# drive_ctrl.net
KiCad netlist of a schematic drawn in EAGLE
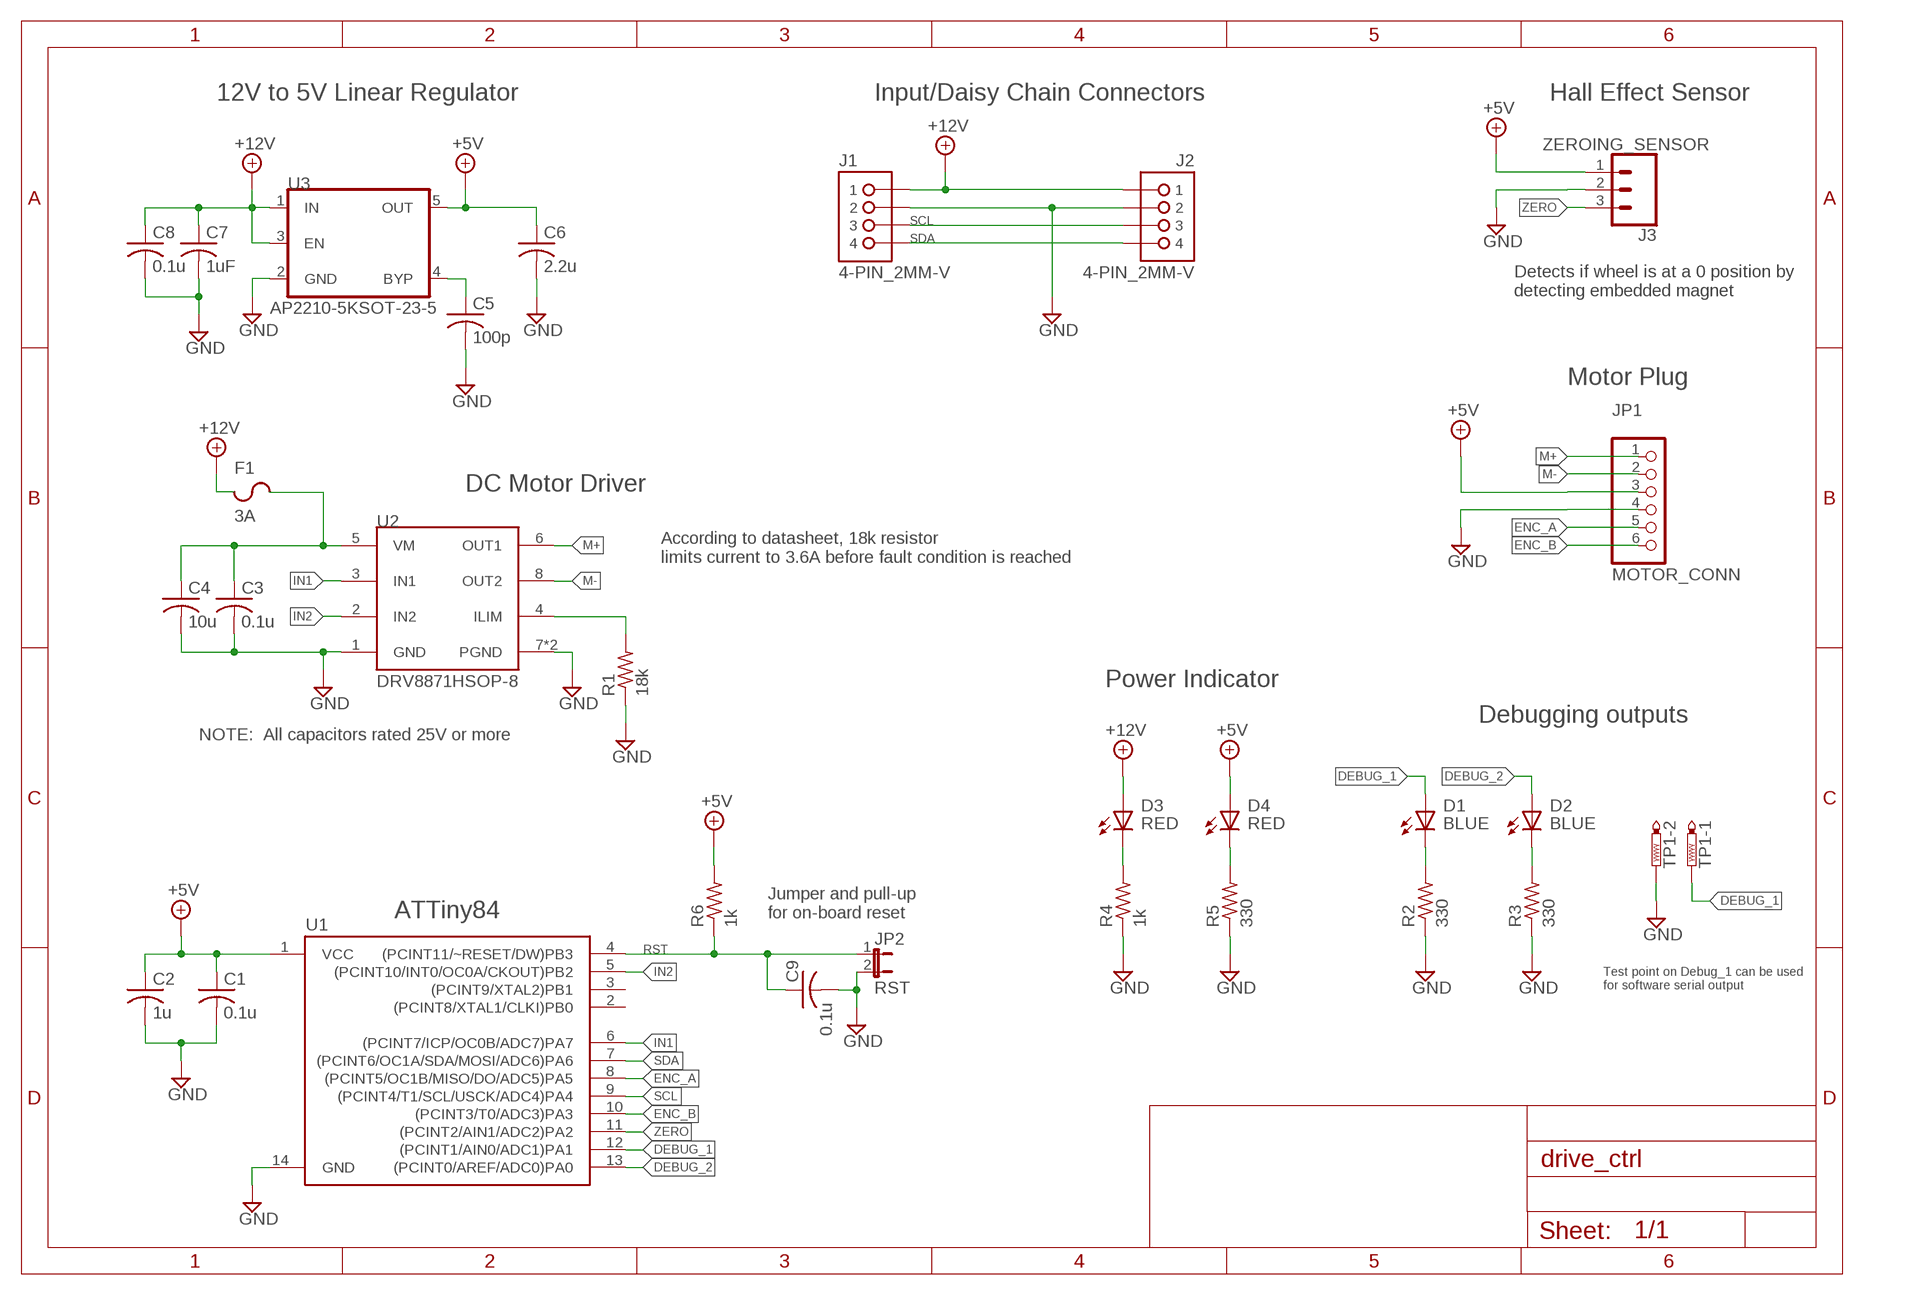
[diagram p0: schematic, sheet 1]

(export (version "E")
  (design (tool "Eeschema 10.0.6"))
  (components
    (comp (ref "C1")
      (value "0.1u")
      (footprint "eagle-import:C0603")
      (libsource (lib "eagle-import") (part "C-USC0603"))
    )
    (comp (ref "C2")
      (value "1u")
      (footprint "eagle-import:C0603")
      (libsource (lib "eagle-import") (part "C-USC0603"))
    )
    (comp (ref "C3")
      (value "0.1u")
      (footprint "eagle-import:C0603")
      (libsource (lib "eagle-import") (part "C-USC0603"))
    )
    (comp (ref "C4")
      (value "10u")
      (footprint "eagle-import:C0603")
      (libsource (lib "eagle-import") (part "C-USC0603"))
    )
    (comp (ref "C5")
      (value "100p")
      (footprint "eagle-import:C0603")
      (libsource (lib "eagle-import") (part "C-USC0603"))
    )
    (comp (ref "C6")
      (value "2.2u")
      (footprint "eagle-import:C0603")
      (libsource (lib "eagle-import") (part "C-USC0603"))
    )
    (comp (ref "C7")
      (value "1uF")
      (footprint "eagle-import:C0603")
      (libsource (lib "eagle-import") (part "C-USC0603"))
    )
    (comp (ref "C8")
      (value "0.1u")
      (footprint "eagle-import:C0603")
      (libsource (lib "eagle-import") (part "C-USC0603"))
    )
    (comp (ref "C9")
      (value "0.1u")
      (footprint "eagle-import:C0603")
      (libsource (lib "eagle-import") (part "C-USC0603"))
    )
    (comp (ref "D1")
      (value "BLUE")
      (footprint "eagle-import:CHIP-LED0603")
      (fields (field (name "MPN") "LTST-C191TBKT"))
      (libsource (lib "eagle-import") (part "LED-SMD-BLUE"))
    )
    (comp (ref "D2")
      (value "BLUE")
      (footprint "eagle-import:CHIP-LED0603")
      (fields (field (name "MPN") "LTST-C191TBKT"))
      (libsource (lib "eagle-import") (part "LED-SMD-BLUE"))
    )
    (comp (ref "D3")
      (value "RED")
      (footprint "eagle-import:CHIP-LED0603")
      (fields (field (name "MPN") "LTST-C191KRKT"))
      (libsource (lib "eagle-import") (part "LED-SMD-RED"))
    )
    (comp (ref "D4")
      (value "RED")
      (footprint "eagle-import:CHIP-LED0603")
      (fields (field (name "MPN") "LTST-C191KRKT"))
      (libsource (lib "eagle-import") (part "LED-SMD-RED"))
    )
    (comp (ref "F1")
      (value "3A")
      (footprint "eagle-import:F1206")
      (libsource (lib "eagle-import") (part "CHIP_FUSE1206"))
    )
    (comp (ref "J1")
      (value "4-PIN_2MM-V")
      (footprint "eagle-import:2MM-4-V")
      (libsource (lib "eagle-import") (part "4-PIN_2MM-V"))
    )
    (comp (ref "J2")
      (value "4-PIN_2MM-V")
      (footprint "eagle-import:2MM-4-V")
      (libsource (lib "eagle-import") (part "4-PIN_2MM-V"))
    )
    (comp (ref "J3")
      (value "ZEROING_SENSOR")
      (footprint "eagle-import:1X03")
      (libsource (lib "eagle-import") (part "CONN_03"))
    )
    (comp (ref "JP1")
      (value "MOTOR_CONN")
      (footprint "eagle-import:1X06")
      (libsource (lib "eagle-import") (part "PINHD-1X6"))
    )
    (comp (ref "JP2")
      (value "RST")
      (footprint "eagle-import:JP1")
      (libsource (lib "eagle-import") (part "JP1E"))
    )
    (comp (ref "R1")
      (value "18k")
      (footprint "eagle-import:R0603")
      (libsource (lib "eagle-import") (part "R-US_R0603"))
    )
    (comp (ref "R2")
      (value "330")
      (footprint "eagle-import:R0603")
      (libsource (lib "eagle-import") (part "R-US_R0603"))
    )
    (comp (ref "R3")
      (value "330")
      (footprint "eagle-import:R0603")
      (libsource (lib "eagle-import") (part "R-US_R0603"))
    )
    (comp (ref "R4")
      (value "1k")
      (footprint "eagle-import:R0603")
      (libsource (lib "eagle-import") (part "R-US_R0603"))
    )
    (comp (ref "R5")
      (value "330")
      (footprint "eagle-import:R0603")
      (libsource (lib "eagle-import") (part "R-US_R0603"))
    )
    (comp (ref "R6")
      (value "1k")
      (footprint "eagle-import:R0603")
      (libsource (lib "eagle-import") (part "R-US_R0603"))
    )
    (comp (ref "TP1")
      (value "PTR2")
      (footprint "eagle-import:P2-38-17")
      (libsource (lib "eagle-import") (part "PTR2"))
    )
    (comp (ref "U1")
      (value "ATTINY84ATTINY84-20PU")
      (footprint "eagle-import:DIP14")
      (libsource (lib "eagle-import") (part "ATTINY84ATTINY84-20PU"))
    )
    (comp (ref "U2")
      (value "DRV8871HSOP-8")
      (footprint "eagle-import:SOIC127P600X170-9T240X310N")
      (libsource (lib "eagle-import") (part "DRV8871HSOP-8"))
    )
    (comp (ref "U3")
      (value "AP2210-5KSOT-23-5")
      (footprint "eagle-import:SOT95P282X145-5N")
      (libsource (lib "eagle-import") (part "AP2210-5KSOT-23-5"))
    )
  )
  (nets
    (net (code "1") (name "+5V") (class "Default")
      (node (ref "C1") (pin "1") (pinfunction "1_1") (pintype "passive"))
      (node (ref "C2") (pin "1") (pinfunction "1_1") (pintype "passive"))
      (node (ref "C6") (pin "1") (pinfunction "1_1") (pintype "passive"))
      (node (ref "D4") (pin "A") (pinfunction "A_A") (pintype "passive"))
      (node (ref "J3") (pin "1") (pinfunction "1_1") (pintype "passive"))
      (node (ref "JP1") (pin "3") (pinfunction "3_3") (pintype "passive"))
      (node (ref "R6") (pin "2") (pinfunction "2_2") (pintype "passive"))
      (node (ref "U1") (pin "1") (pinfunction "VCC_1") (pintype "bidirectional"))
      (node (ref "U3") (pin "5") (pinfunction "OUT_5") (pintype "power_in"))
    )
    (net (code "2") (name "+12V") (class "Default")
      (node (ref "C7") (pin "1") (pinfunction "1_1") (pintype "passive"))
      (node (ref "C8") (pin "1") (pinfunction "1_1") (pintype "passive"))
      (node (ref "D3") (pin "A") (pinfunction "A_A") (pintype "passive"))
      (node (ref "F1") (pin "1") (pinfunction "1_1") (pintype "bidirectional"))
      (node (ref "J1") (pin "1") (pinfunction "1_1") (pintype "passive"))
      (node (ref "J2") (pin "1") (pinfunction "1_1") (pintype "passive"))
      (node (ref "U3") (pin "1") (pinfunction "IN_1") (pintype "power_in"))
      (node (ref "U3") (pin "3") (pinfunction "EN_3") (pintype "input"))
    )
    (net (code "3") (name "/RST") (class "Default")
      (node (ref "C9") (pin "1") (pinfunction "1_1") (pintype "passive"))
      (node (ref "JP2") (pin "1") (pinfunction "1_1") (pintype "passive"))
      (node (ref "R6") (pin "1") (pinfunction "1_1") (pintype "passive"))
      (node (ref "U1") (pin "4") (pinfunction "(PCINT11/~{RESET/DW})PB3_4") (pintype "bidirectional"))
    )
    (net (code "4") (name "DEBUG_1") (class "Default")
      (node (ref "D1") (pin "A") (pinfunction "A_A") (pintype "passive"))
      (node (ref "TP1") (pin "TP-1") (pinfunction "TP_TP-1") (pintype "input"))
      (node (ref "U1") (pin "12") (pinfunction "(PCINT1/AIN0/ADC1)PA1_12") (pintype "bidirectional"))
    )
    (net (code "5") (name "DEBUG_2") (class "Default")
      (node (ref "D2") (pin "A") (pinfunction "A_A") (pintype "passive"))
      (node (ref "U1") (pin "13") (pinfunction "(PCINT0/AREF/ADC0)PA0_13") (pintype "bidirectional"))
    )
    (net (code "6") (name "ENC_A") (class "Default")
      (node (ref "JP1") (pin "5") (pinfunction "5_5") (pintype "passive"))
      (node (ref "U1") (pin "8") (pinfunction "(PCINT5/OC1B/MISO/DO/ADC5)PA5_8") (pintype "bidirectional"))
    )
    (net (code "7") (name "ENC_B") (class "Default")
      (node (ref "JP1") (pin "6") (pinfunction "6_6") (pintype "passive"))
      (node (ref "U1") (pin "10") (pinfunction "(PCINT3/T0/ADC3)PA3_10") (pintype "bidirectional"))
    )
    (net (code "8") (name "GND") (class "Default")
      (node (ref "C1") (pin "2") (pinfunction "2_2") (pintype "passive"))
      (node (ref "C2") (pin "2") (pinfunction "2_2") (pintype "passive"))
      (node (ref "C3") (pin "2") (pinfunction "2_2") (pintype "passive"))
      (node (ref "C4") (pin "2") (pinfunction "2_2") (pintype "passive"))
      (node (ref "C5") (pin "2") (pinfunction "2_2") (pintype "passive"))
      (node (ref "C6") (pin "2") (pinfunction "2_2") (pintype "passive"))
      (node (ref "C7") (pin "2") (pinfunction "2_2") (pintype "passive"))
      (node (ref "C8") (pin "2") (pinfunction "2_2") (pintype "passive"))
      (node (ref "C9") (pin "2") (pinfunction "2_2") (pintype "passive"))
      (node (ref "J1") (pin "2") (pinfunction "2_2") (pintype "passive"))
      (node (ref "J2") (pin "2") (pinfunction "2_2") (pintype "passive"))
      (node (ref "J3") (pin "2") (pinfunction "2_2") (pintype "passive"))
      (node (ref "JP1") (pin "4") (pinfunction "4_4") (pintype "passive"))
      (node (ref "JP2") (pin "2") (pinfunction "2_2") (pintype "passive"))
      (node (ref "R1") (pin "1") (pinfunction "1_1") (pintype "passive"))
      (node (ref "R2") (pin "1") (pinfunction "1_1") (pintype "passive"))
      (node (ref "R3") (pin "1") (pinfunction "1_1") (pintype "passive"))
      (node (ref "R4") (pin "1") (pinfunction "1_1") (pintype "passive"))
      (node (ref "R5") (pin "1") (pinfunction "1_1") (pintype "passive"))
      (node (ref "TP1") (pin "TP-2") (pinfunction "TP_TP-2") (pintype "input"))
      (node (ref "U1") (pin "14") (pinfunction "GND_14") (pintype "bidirectional"))
      (node (ref "U2") (pin "1") (pinfunction "GND_1") (pintype "power_in"))
      (node (ref "U2") (pin "7") (pinfunction "PGND_7") (pintype "power_in"))
      (node (ref "U2") (pin "9") (pinfunction "PGND_9") (pintype "power_in"))
      (node (ref "U3") (pin "2") (pinfunction "GND_2") (pintype "power_in"))
    )
    (net (code "9") (name "IN1") (class "Default")
      (node (ref "U1") (pin "6") (pinfunction "(PCINT7/ICP/OC0B/ADC7)PA7_6") (pintype "bidirectional"))
      (node (ref "U2") (pin "3") (pinfunction "IN1_3") (pintype "input"))
    )
    (net (code "10") (name "IN2") (class "Default")
      (node (ref "U1") (pin "5") (pinfunction "(PCINT10/INT0/OC0A/CKOUT)PB2_5") (pintype "bidirectional"))
      (node (ref "U2") (pin "2") (pinfunction "IN2_2") (pintype "input"))
    )
    (net (code "11") (name "M+") (class "Default")
      (node (ref "JP1") (pin "1") (pinfunction "1_1") (pintype "passive"))
      (node (ref "U2") (pin "6") (pinfunction "OUT1_6") (pintype "output"))
    )
    (net (code "12") (name "M-") (class "Default")
      (node (ref "JP1") (pin "2") (pinfunction "2_2") (pintype "passive"))
      (node (ref "U2") (pin "8") (pinfunction "OUT2_8") (pintype "output"))
    )
    (net (code "13") (name "Net-(D1-K)") (class "Default")
      (node (ref "D1") (pin "C") (pinfunction "K_C") (pintype "passive"))
      (node (ref "R2") (pin "2") (pinfunction "2_2") (pintype "passive"))
    )
    (net (code "14") (name "Net-(D2-K)") (class "Default")
      (node (ref "D2") (pin "C") (pinfunction "K_C") (pintype "passive"))
      (node (ref "R3") (pin "2") (pinfunction "2_2") (pintype "passive"))
    )
    (net (code "15") (name "Net-(D3-K)") (class "Default")
      (node (ref "D3") (pin "C") (pinfunction "K_C") (pintype "passive"))
      (node (ref "R4") (pin "2") (pinfunction "2_2") (pintype "passive"))
    )
    (net (code "16") (name "Net-(D4-K)") (class "Default")
      (node (ref "D4") (pin "C") (pinfunction "K_C") (pintype "passive"))
      (node (ref "R5") (pin "2") (pinfunction "2_2") (pintype "passive"))
    )
    (net (code "17") (name "Net-(U2-ILIM)") (class "Default")
      (node (ref "R1") (pin "2") (pinfunction "2_2") (pintype "passive"))
      (node (ref "U2") (pin "4") (pinfunction "ILIM_4") (pintype "passive"))
    )
    (net (code "18") (name "Net-(U2-VM)") (class "Default")
      (node (ref "C3") (pin "1") (pinfunction "1_1") (pintype "passive"))
      (node (ref "C4") (pin "1") (pinfunction "1_1") (pintype "passive"))
      (node (ref "F1") (pin "2") (pinfunction "2_2") (pintype "bidirectional"))
      (node (ref "U2") (pin "5") (pinfunction "VM_5") (pintype "power_in"))
    )
    (net (code "19") (name "Net-(U3-BYP)") (class "Default")
      (node (ref "C5") (pin "1") (pinfunction "1_1") (pintype "passive"))
      (node (ref "U3") (pin "4") (pinfunction "BYP_4") (pintype "passive"))
    )
    (net (code "20") (name "SCL") (class "Default")
      (node (ref "J1") (pin "3") (pinfunction "3_3") (pintype "passive"))
      (node (ref "J2") (pin "3") (pinfunction "3_3") (pintype "passive"))
      (node (ref "U1") (pin "9") (pinfunction "(PCINT4/T1/SCL/USCK/ADC4)PA4_9") (pintype "bidirectional"))
    )
    (net (code "21") (name "SDA") (class "Default")
      (node (ref "J1") (pin "4") (pinfunction "4_4") (pintype "passive"))
      (node (ref "J2") (pin "4") (pinfunction "4_4") (pintype "passive"))
      (node (ref "U1") (pin "7") (pinfunction "(PCINT6/OC1A/SDA/MOSI/ADC6)PA6_7") (pintype "bidirectional"))
    )
    (net (code "22") (name "ZERO") (class "Default")
      (node (ref "J3") (pin "3") (pinfunction "3_3") (pintype "passive"))
      (node (ref "U1") (pin "11") (pinfunction "(PCINT2/AIN1/ADC2)PA2_11") (pintype "bidirectional"))
    )
    (net (code "23") (name "unconnected-(U1-(PCINT8{slash}XTAL1{slash}CLKI)PB0-Pad2)") (class "Default")
      (node (ref "U1") (pin "2") (pinfunction "(PCINT8/XTAL1/CLKI)PB0_2") (pintype "bidirectional"))
    )
    (net (code "24") (name "unconnected-(U1-(PCINT9{slash}XTAL2)PB1-Pad3)") (class "Default")
      (node (ref "U1") (pin "3") (pinfunction "(PCINT9/XTAL2)PB1_3") (pintype "bidirectional"))
    )
  )
)
